# EBAZ4205__EPD_TX.net
KiCad netlist of a schematic drawn in Altium Designer
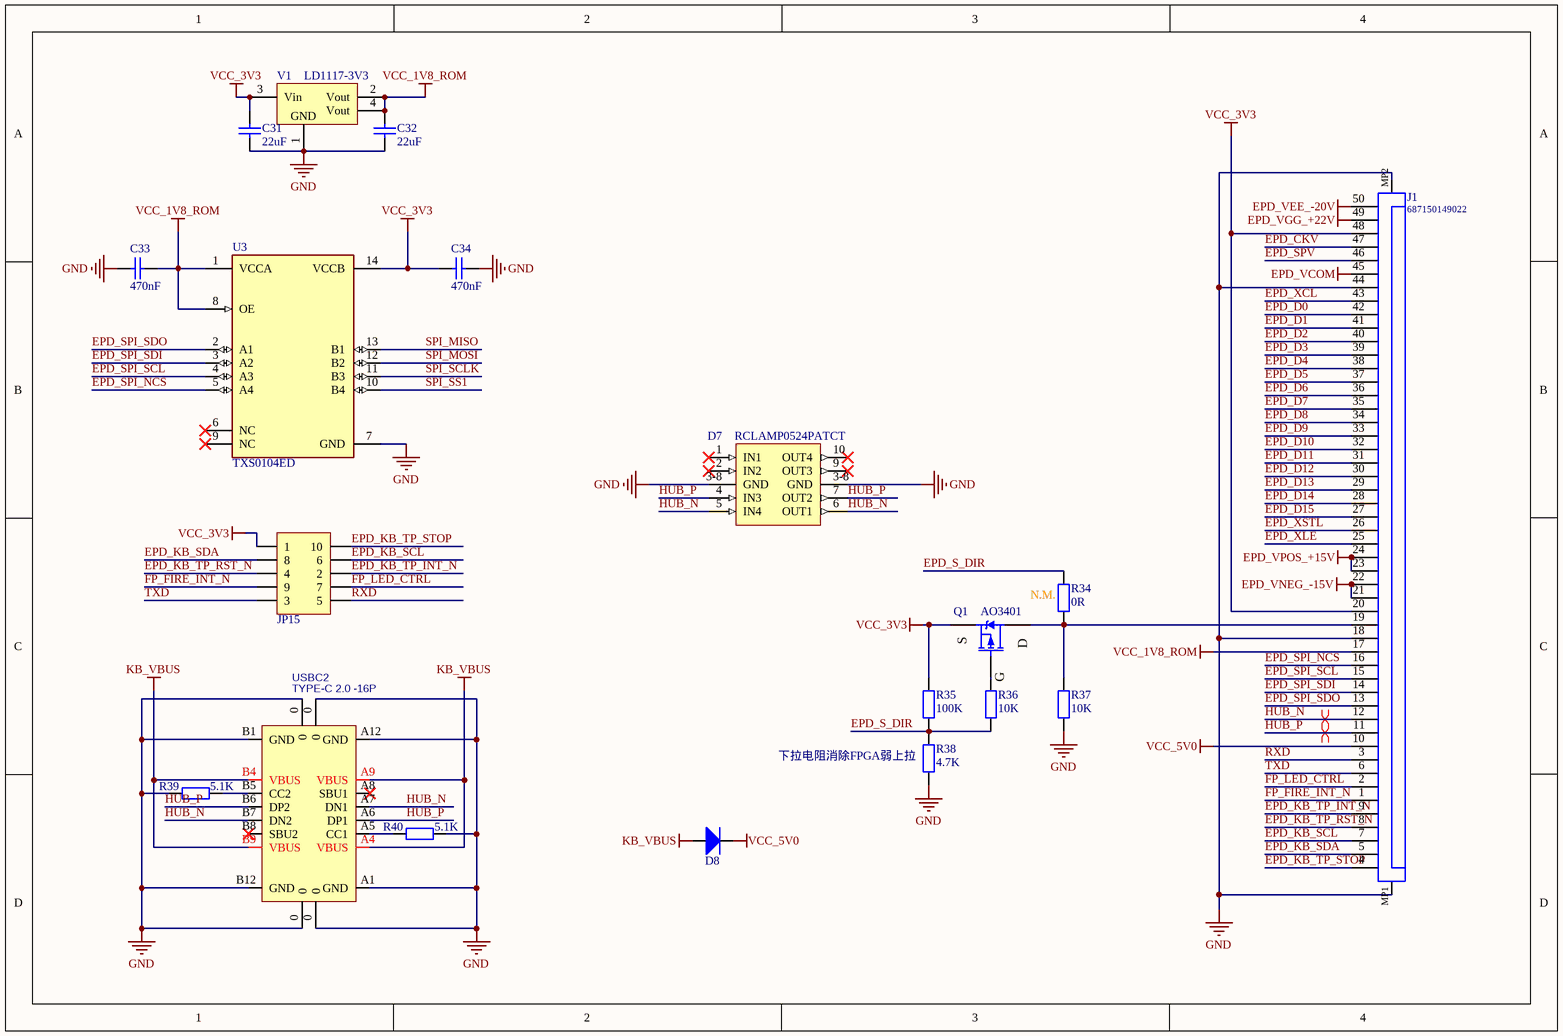
[diagram p0: EBAZ4205扩展_EPD_TX.SchDoc]

(export (version "E")
  (design (tool "Eeschema 10.0.6"))
  (components
    (comp (ref "C31")
      (value "22uF")
      (footprint "C0603_L")
      (description "贴片电容")
      (libsource (lib "0.1 - 电阻-电容-电感-磁珠-电位器") (part "C"))
    )
    (comp (ref "C32")
      (value "22uF")
      (footprint "C0603_L")
      (description "贴片电容")
      (libsource (lib "0.1 - 电阻-电容-电感-磁珠-电位器") (part "C"))
    )
    (comp (ref "C33")
      (value "470nF")
      (footprint "C0603_L")
      (description "贴片电容")
      (libsource (lib "0.1 - 电阻-电容-电感-磁珠-电位器") (part "C"))
    )
    (comp (ref "C34")
      (value "470nF")
      (footprint "C0603_L")
      (description "贴片电容")
      (libsource (lib "0.1 - 电阻-电容-电感-磁珠-电位器") (part "C"))
    )
    (comp (ref "D7")
      (value "RCLAMP0524PATCT")
      (footprint "FP-SLP2510P8-MFG")
      (description "TVS DIODE 5V 15V SLP2510P8")
      (libsource (lib "AD") (part "RCLAMP0524PATCT"))
    )
    (comp (ref "D8")
      (value "TVS")
      (footprint "SOD-123")
      (description "TVS通用")
      (libsource (lib "0.2 - 二极管-TVS-ESD-整流桥") (part "TVS"))
    )
    (comp (ref "J1")
      (value "687150149022")
      (footprint "687150149022")
      (description "SMT ZIF Connectors Hinge Type WR-FPC, Horizontal, Bottom Contact, pitch 0.5 mm, 50 pins")
      (fields (field (name "MANUFACTURER") "Wurth Elektronik") (field (name "PUBLISHER") "WurthElektronik"))
      (libsource (lib "Altium Content Vault") (part "WE-6871501XXX22-50"))
    )
    (comp (ref "JP15")
      (value "Header 5X2")
      (footprint "HDR2.54-LI-2x5P")
      (description "5*2P接插件")
      (libsource (lib "5.5 - 接插件-脚距2.54 (100mil) ") (part "Header 5X2"))
    )
    (comp (ref "Q1")
      (value "AO3401")
      (footprint "SOT23-3N")
      (description "P沟道 30V/4.2A")
      (libsource (lib "0.4 - 三极管-场效应管-可控硅") (part "AO3401"))
    )
    (comp (ref "R34")
      (value "0R")
      (footprint "R0402_L")
      (description "贴片电阻")
      (libsource (lib "0.1 - 电阻-电容-电感-磁珠-电位器") (part "R"))
    )
    (comp (ref "R35")
      (value "100K")
      (footprint "R0402_L")
      (description "贴片电阻")
      (libsource (lib "0.1 - 电阻-电容-电感-磁珠-电位器") (part "R"))
    )
    (comp (ref "R36")
      (value "10K")
      (footprint "R0402_L")
      (description "贴片电阻")
      (libsource (lib "0.1 - 电阻-电容-电感-磁珠-电位器") (part "R"))
    )
    (comp (ref "R37")
      (value "10K")
      (footprint "R0402_L")
      (description "贴片电阻")
      (libsource (lib "0.1 - 电阻-电容-电感-磁珠-电位器") (part "R"))
    )
    (comp (ref "R38")
      (value "4.7K")
      (footprint "R0402_L")
      (description "贴片电阻")
      (fields (field (name "4.作者声明") "旨为整合最全库集,欢迎转载,禁止商用！-冰凌猫") (field (name "1.库作者") "冰凌猫"))
      (libsource (lib "0.1 - 电阻-电容-电感-磁珠-电位器") (part "R"))
    )
    (comp (ref "R39")
      (value "5.1K")
      (footprint "R0402_L")
      (description "贴片电阻")
      (libsource (lib "0.1 - 电阻-电容-电感-磁珠-电位器") (part "R"))
    )
    (comp (ref "R40")
      (value "5.1K")
      (footprint "R0402_L")
      (description "贴片电阻")
      (libsource (lib "0.1 - 电阻-电容-电感-磁珠-电位器") (part "R"))
    )
    (comp (ref "U3")
      (value "TXS0104ED")
      (footprint "FP-D0014A-IPC_C")
      (description "IC TRNSLTR BIDIRECTIONAL 14SOIC")
      (fields
        (field (name "MANUFACTURER") "Texas Instruments")
        (field (name "OCTOPART") "https://octopart.com/txs0104ed-texas+instruments-1486620")
      )
      (libsource (lib "Altium Content Vault") (part "cce7ffc6ce8c0ee524f97eee64c246b"))
    )
    (comp (ref "USBC2")
      (value "TYPE-C 2.0 -16P")
      (footprint "USB-C-SMD_16P")
      (description "USB2.0 Type-C 16Pin  母座")
      (libsource (lib "0.8 - 以太网-音频-Type-C USB插座") (part "USB2.0_Type-C_16Pin"))
    )
    (comp (ref "V1")
      (value "LD1117-3V3")
      (footprint "SOT223_L")
      (description "三端稳压芯片")
      (libsource (lib "1.1 - 电源类芯片") (part "LD1117"))
    )
  )
  (nets
    (net (code "1") (name "/EPD_CKV") (class "Default")
      (node (ref "J1") (pin "47") (pinfunction "47_47") (pintype "passive"))
    )
    (net (code "2") (name "/EPD_D0") (class "Default")
      (node (ref "J1") (pin "42") (pinfunction "42_42") (pintype "passive"))
    )
    (net (code "3") (name "/EPD_D1") (class "Default")
      (node (ref "J1") (pin "41") (pinfunction "41_41") (pintype "passive"))
    )
    (net (code "4") (name "/EPD_D2") (class "Default")
      (node (ref "J1") (pin "40") (pinfunction "40_40") (pintype "passive"))
    )
    (net (code "5") (name "/EPD_D3") (class "Default")
      (node (ref "J1") (pin "39") (pinfunction "39_39") (pintype "passive"))
    )
    (net (code "6") (name "/EPD_D4") (class "Default")
      (node (ref "J1") (pin "38") (pinfunction "38_38") (pintype "passive"))
    )
    (net (code "7") (name "/EPD_D5") (class "Default")
      (node (ref "J1") (pin "37") (pinfunction "37_37") (pintype "passive"))
    )
    (net (code "8") (name "/EPD_D6") (class "Default")
      (node (ref "J1") (pin "36") (pinfunction "36_36") (pintype "passive"))
    )
    (net (code "9") (name "/EPD_D7") (class "Default")
      (node (ref "J1") (pin "35") (pinfunction "35_35") (pintype "passive"))
    )
    (net (code "10") (name "/EPD_D8") (class "Default")
      (node (ref "J1") (pin "34") (pinfunction "34_34") (pintype "passive"))
    )
    (net (code "11") (name "/EPD_D9") (class "Default")
      (node (ref "J1") (pin "33") (pinfunction "33_33") (pintype "passive"))
    )
    (net (code "12") (name "/EPD_D10") (class "Default")
      (node (ref "J1") (pin "32") (pinfunction "32_32") (pintype "passive"))
    )
    (net (code "13") (name "/EPD_D11") (class "Default")
      (node (ref "J1") (pin "31") (pinfunction "31_31") (pintype "passive"))
    )
    (net (code "14") (name "/EPD_D12") (class "Default")
      (node (ref "J1") (pin "30") (pinfunction "30_30") (pintype "passive"))
    )
    (net (code "15") (name "/EPD_D13") (class "Default")
      (node (ref "J1") (pin "29") (pinfunction "29_29") (pintype "passive"))
    )
    (net (code "16") (name "/EPD_D14") (class "Default")
      (node (ref "J1") (pin "28") (pinfunction "28_28") (pintype "passive"))
    )
    (net (code "17") (name "/EPD_D15") (class "Default")
      (node (ref "J1") (pin "27") (pinfunction "27_27") (pintype "passive"))
    )
    (net (code "18") (name "/EPD_KB_SCL") (class "Default")
      (node (ref "J1") (pin "7") (pinfunction "7_7") (pintype "passive"))
      (node (ref "JP15") (pin "6") (pinfunction "6_6") (pintype "passive"))
    )
    (net (code "19") (name "/EPD_KB_SDA") (class "Default")
      (node (ref "J1") (pin "5") (pinfunction "5_5") (pintype "passive"))
      (node (ref "JP15") (pin "8") (pinfunction "8_8") (pintype "passive"))
    )
    (net (code "20") (name "/EPD_KB_TP_INT_N") (class "Default")
      (node (ref "J1") (pin "9") (pinfunction "9_9") (pintype "passive"))
      (node (ref "JP15") (pin "2") (pinfunction "2_2") (pintype "passive"))
    )
    (net (code "21") (name "/EPD_KB_TP_RST_N") (class "Default")
      (node (ref "J1") (pin "8") (pinfunction "8_8") (pintype "passive"))
      (node (ref "JP15") (pin "4") (pinfunction "4_4") (pintype "passive"))
    )
    (net (code "22") (name "/EPD_KB_TP_STOP") (class "Default")
      (node (ref "J1") (pin "4") (pinfunction "4_4") (pintype "passive"))
      (node (ref "JP15") (pin "10") (pinfunction "10_10") (pintype "passive"))
    )
    (net (code "23") (name "/EPD_SPI_NCS") (class "Default")
      (node (ref "J1") (pin "16") (pinfunction "16_16") (pintype "passive"))
      (node (ref "U3") (pin "5") (pinfunction "A4_5") (pintype "bidirectional"))
    )
    (net (code "24") (name "/EPD_SPI_SCL") (class "Default")
      (node (ref "J1") (pin "15") (pinfunction "15_15") (pintype "passive"))
      (node (ref "U3") (pin "4") (pinfunction "A3_4") (pintype "bidirectional"))
    )
    (net (code "25") (name "/EPD_SPI_SDI") (class "Default")
      (node (ref "J1") (pin "14") (pinfunction "14_14") (pintype "passive"))
      (node (ref "U3") (pin "3") (pinfunction "A2_3") (pintype "bidirectional"))
    )
    (net (code "26") (name "/EPD_SPI_SDO") (class "Default")
      (node (ref "J1") (pin "13") (pinfunction "13_13") (pintype "passive"))
      (node (ref "U3") (pin "2") (pinfunction "A1_2") (pintype "bidirectional"))
    )
    (net (code "27") (name "/EPD_SPV") (class "Default")
      (node (ref "J1") (pin "46") (pinfunction "46_46") (pintype "passive"))
    )
    (net (code "28") (name "/EPD_S_DIR") (class "Default")
      (node (ref "R34") (pin "1") (pinfunction "1_1") (pintype "passive"))
      (node (ref "R35") (pin "2") (pinfunction "2_2") (pintype "passive"))
      (node (ref "R36") (pin "2") (pinfunction "2_2") (pintype "passive"))
      (node (ref "R38") (pin "2") (pinfunction "2_2") (pintype "passive"))
    )
    (net (code "29") (name "/EPD_XCL") (class "Default")
      (node (ref "J1") (pin "43") (pinfunction "43_43") (pintype "passive"))
    )
    (net (code "30") (name "/EPD_XLE") (class "Default")
      (node (ref "J1") (pin "25") (pinfunction "25_25") (pintype "passive"))
    )
    (net (code "31") (name "/EPD_XSTL") (class "Default")
      (node (ref "J1") (pin "26") (pinfunction "26_26") (pintype "passive"))
    )
    (net (code "32") (name "/FP_FIRE_INT_N") (class "Default")
      (node (ref "J1") (pin "1") (pinfunction "1_1") (pintype "passive"))
      (node (ref "JP15") (pin "9") (pinfunction "9_9") (pintype "passive"))
    )
    (net (code "33") (name "/FP_LED_CTRL") (class "Default")
      (node (ref "J1") (pin "2") (pinfunction "2_2") (pintype "passive"))
      (node (ref "JP15") (pin "7") (pinfunction "7_7") (pintype "passive"))
    )
    (net (code "34") (name "/HUB_N") (class "Default")
      (node (ref "D7") (pin "5") (pinfunction "IN4_5") (pintype "input"))
      (node (ref "D7") (pin "6") (pinfunction "OUT1_6") (pintype "output"))
      (node (ref "J1") (pin "12") (pinfunction "12_12") (pintype "passive"))
      (node (ref "USBC2") (pin "A7") (pinfunction "DN1_A7") (pintype "passive"))
      (node (ref "USBC2") (pin "B7") (pinfunction "DN2_B7") (pintype "passive"))
    )
    (net (code "35") (name "/HUB_P") (class "Default")
      (node (ref "D7") (pin "4") (pinfunction "IN3_4") (pintype "input"))
      (node (ref "D7") (pin "7") (pinfunction "OUT2_7") (pintype "output"))
      (node (ref "J1") (pin "11") (pinfunction "11_11") (pintype "passive"))
      (node (ref "USBC2") (pin "A6") (pinfunction "DP1_A6") (pintype "passive"))
      (node (ref "USBC2") (pin "B6") (pinfunction "DP2_B6") (pintype "passive"))
    )
    (net (code "36") (name "/RXD") (class "Default")
      (node (ref "J1") (pin "3") (pinfunction "3_3") (pintype "passive"))
      (node (ref "JP15") (pin "5") (pinfunction "5_5") (pintype "passive"))
    )
    (net (code "37") (name "/SPI_MISO") (class "Default")
      (node (ref "U3") (pin "13") (pinfunction "B1_13") (pintype "bidirectional"))
    )
    (net (code "38") (name "/SPI_MOSI") (class "Default")
      (node (ref "U3") (pin "12") (pinfunction "B2_12") (pintype "bidirectional"))
    )
    (net (code "39") (name "/SPI_SCLK") (class "Default")
      (node (ref "U3") (pin "11") (pinfunction "B3_11") (pintype "bidirectional"))
    )
    (net (code "40") (name "/SPI_SS1") (class "Default")
      (node (ref "U3") (pin "10") (pinfunction "B4_10") (pintype "bidirectional"))
    )
    (net (code "41") (name "/TXD") (class "Default")
      (node (ref "J1") (pin "6") (pinfunction "6_6") (pintype "passive"))
      (node (ref "JP15") (pin "3") (pinfunction "3_3") (pintype "passive"))
    )
    (net (code "42") (name "EPD_VCOM") (class "Default")
      (node (ref "J1") (pin "45") (pinfunction "45_45") (pintype "passive"))
    )
    (net (code "43") (name "EPD_VEE_-20V") (class "Default")
      (node (ref "J1") (pin "50") (pinfunction "50_50") (pintype "passive"))
    )
    (net (code "44") (name "EPD_VGG_+22V") (class "Default")
      (node (ref "J1") (pin "49") (pinfunction "49_49") (pintype "passive"))
    )
    (net (code "45") (name "EPD_VNEG_-15V") (class "Default")
      (node (ref "J1") (pin "21") (pinfunction "21_21") (pintype "passive"))
      (node (ref "J1") (pin "22") (pinfunction "22_22") (pintype "passive"))
    )
    (net (code "46") (name "EPD_VPOS_+15V") (class "Default")
      (node (ref "J1") (pin "23") (pinfunction "23_23") (pintype "passive"))
      (node (ref "J1") (pin "24") (pinfunction "24_24") (pintype "passive"))
    )
    (net (code "47") (name "GND") (class "Default")
      (node (ref "C31") (pin "1") (pinfunction "1_1") (pintype "passive"))
      (node (ref "C32") (pin "1") (pinfunction "1_1") (pintype "passive"))
      (node (ref "C33") (pin "1") (pinfunction "1_1") (pintype "passive"))
      (node (ref "C34") (pin "2") (pinfunction "2_2") (pintype "passive"))
      (node (ref "D7") (pin "3-8") (pinfunction "GND_3-8") (pintype "tri_state"))
      (node (ref "J1") (pin "18") (pinfunction "18_18") (pintype "passive"))
      (node (ref "J1") (pin "44") (pinfunction "44_44") (pintype "passive"))
      (node (ref "J1") (pin "MP1") (pinfunction "MP1_MP1") (pintype "passive"))
      (node (ref "J1") (pin "MP2") (pinfunction "MP2_MP2") (pintype "passive"))
      (node (ref "R37") (pin "2") (pinfunction "2_2") (pintype "passive"))
      (node (ref "R38") (pin "1") (pinfunction "1_1") (pintype "passive"))
      (node (ref "R39") (pin "2") (pinfunction "2_2") (pintype "passive"))
      (node (ref "R40") (pin "1") (pinfunction "1_1") (pintype "passive"))
      (node (ref "U3") (pin "7") (pinfunction "GND_7") (pintype "power_in"))
      (node (ref "USBC2") (pin "0") (pinfunction "0_0") (pintype "passive"))
      (node (ref "USBC2") (pin "A1") (pinfunction "GND_A1") (pintype "passive"))
      (node (ref "USBC2") (pin "A12") (pinfunction "GND_A12") (pintype "passive"))
      (node (ref "USBC2") (pin "B1") (pinfunction "GND_B1") (pintype "passive"))
      (node (ref "USBC2") (pin "B12") (pinfunction "GND_B12") (pintype "passive"))
      (node (ref "V1") (pin "1") (pinfunction "GND_1") (pintype "passive"))
    )
    (net (code "48") (name "KB_VBUS") (class "Default")
      (node (ref "D8") (pin "1") (pinfunction "A_1") (pintype "passive"))
      (node (ref "USBC2") (pin "A4") (pinfunction "VBUS_A4") (pintype "passive"))
      (node (ref "USBC2") (pin "A9") (pinfunction "VBUS_A9") (pintype "passive"))
      (node (ref "USBC2") (pin "B4") (pinfunction "VBUS_B4") (pintype "passive"))
      (node (ref "USBC2") (pin "B9") (pinfunction "VBUS_B9") (pintype "passive"))
    )
    (net (code "49") (name "Net-(Q1-D)") (class "Default")
      (node (ref "J1") (pin "19") (pinfunction "19_19") (pintype "passive"))
      (node (ref "Q1") (pin "3") (pinfunction "D_3") (pintype "passive"))
      (node (ref "R34") (pin "2") (pinfunction "2_2") (pintype "passive"))
      (node (ref "R37") (pin "1") (pinfunction "1_1") (pintype "passive"))
    )
    (net (code "50") (name "Net-(Q1-G)") (class "Default")
      (node (ref "Q1") (pin "1") (pinfunction "G_1") (pintype "passive"))
      (node (ref "R36") (pin "1") (pinfunction "1_1") (pintype "passive"))
    )
    (net (code "51") (name "Net-(USBC2-CC1)") (class "Default")
      (node (ref "R40") (pin "2") (pinfunction "2_2") (pintype "passive"))
      (node (ref "USBC2") (pin "A5") (pinfunction "CC1_A5") (pintype "passive"))
    )
    (net (code "52") (name "Net-(USBC2-CC2)") (class "Default")
      (node (ref "R39") (pin "1") (pinfunction "1_1") (pintype "passive"))
      (node (ref "USBC2") (pin "B5") (pinfunction "CC2_B5") (pintype "passive"))
    )
    (net (code "53") (name "VCC_1V8_ROM") (class "Default")
      (node (ref "C32") (pin "2") (pinfunction "2_2") (pintype "passive"))
      (node (ref "C33") (pin "2") (pinfunction "2_2") (pintype "passive"))
      (node (ref "J1") (pin "17") (pinfunction "17_17") (pintype "passive"))
      (node (ref "U3") (pin "1") (pinfunction "VCCA_1") (pintype "power_in"))
      (node (ref "U3") (pin "8") (pinfunction "OE_8") (pintype "input"))
      (node (ref "V1") (pin "2") (pinfunction "Vout_2") (pintype "passive"))
      (node (ref "V1") (pin "4") (pinfunction "Vout_4") (pintype "passive"))
    )
    (net (code "54") (name "VCC_3V3") (class "Default")
      (node (ref "C31") (pin "2") (pinfunction "2_2") (pintype "passive"))
      (node (ref "C34") (pin "1") (pinfunction "1_1") (pintype "passive"))
      (node (ref "J1") (pin "20") (pinfunction "20_20") (pintype "passive"))
      (node (ref "J1") (pin "48") (pinfunction "48_48") (pintype "passive"))
      (node (ref "JP15") (pin "1") (pinfunction "1_1") (pintype "passive"))
      (node (ref "Q1") (pin "2") (pinfunction "S_2") (pintype "passive"))
      (node (ref "R35") (pin "1") (pinfunction "1_1") (pintype "passive"))
      (node (ref "U3") (pin "14") (pinfunction "VCCB_14") (pintype "power_in"))
      (node (ref "V1") (pin "3") (pinfunction "Vin_3") (pintype "passive"))
    )
    (net (code "55") (name "VCC_5V0") (class "Default")
      (node (ref "D8") (pin "2") (pinfunction "K_2") (pintype "passive"))
      (node (ref "J1") (pin "10") (pinfunction "10_10") (pintype "passive"))
    )
    (net (code "56") (name "unconnected-(D7-IN1-Pad1)") (class "Default")
      (node (ref "D7") (pin "1") (pinfunction "IN1_1") (pintype "input+no_connect"))
    )
    (net (code "57") (name "unconnected-(D7-IN2-Pad2)") (class "Default")
      (node (ref "D7") (pin "2") (pinfunction "IN2_2") (pintype "input+no_connect"))
    )
    (net (code "58") (name "unconnected-(D7-OUT3-Pad9)") (class "Default")
      (node (ref "D7") (pin "9") (pinfunction "OUT3_9") (pintype "output+no_connect"))
    )
    (net (code "59") (name "unconnected-(D7-OUT4-Pad10)") (class "Default")
      (node (ref "D7") (pin "10") (pinfunction "OUT4_10") (pintype "output+no_connect"))
    )
    (net (code "60") (name "unconnected-(U3-NC-Pad6)") (class "Default")
      (node (ref "U3") (pin "6") (pinfunction "NC_6") (pintype "passive+no_connect"))
    )
    (net (code "61") (name "unconnected-(U3-NC-Pad9)") (class "Default")
      (node (ref "U3") (pin "9") (pinfunction "NC_9") (pintype "passive+no_connect"))
    )
    (net (code "62") (name "unconnected-(USBC2-SBU1-PadA8)") (class "Default")
      (node (ref "USBC2") (pin "A8") (pinfunction "SBU1_A8") (pintype "passive+no_connect"))
    )
    (net (code "63") (name "unconnected-(USBC2-SBU2-PadB8)") (class "Default")
      (node (ref "USBC2") (pin "B8") (pinfunction "SBU2_B8") (pintype "passive+no_connect"))
    )
  )
)
